# Input.net
KiCad netlist of a schematic drawn in Altium Designer
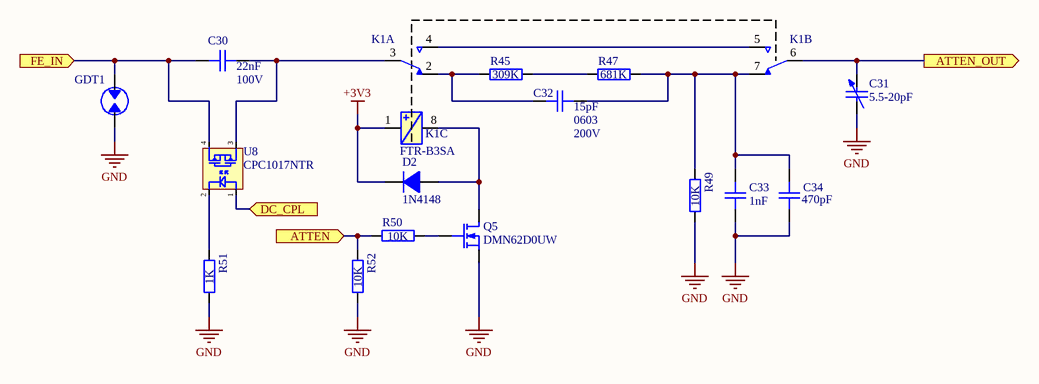
[diagram p0: Input.SchDoc]

(export (version "E")
  (design (tool "Eeschema 10.0.6"))
  (components
    (comp (ref "C30")
      (value "22nF")
      (footprint "GEN_C_0603")
      (fields (field (name "VOLTAGE RATING") "100V"))
      (libsource (lib "DSO") (part "CAP 22nF 100V X7R 0603"))
    )
    (comp (ref "C31")
      (value "5.5-20pF")
      (footprint "EW_TRIMCAP")
      (libsource (lib "DSO") (part "CAP TRIMMER 5.5-20PF 500V"))
    )
    (comp (ref "C32")
      (value "15pF")
      (footprint "GEN_C_0603")
      (fields (field (name "PACKAGE") "0603") (field (name "VOLTAGE RATING") "200V"))
      (libsource (lib "DSO") (part "CAP 15pF 200V C0G 0603"))
    )
    (comp (ref "C33")
      (value "1nF")
      (footprint "GEN_C_0402")
      (libsource (lib "DSO") (part "CAP 1nF 50V C0G 0402"))
    )
    (comp (ref "C34")
      (value "470pF")
      (footprint "GEN_C_0402")
      (libsource (lib "DSO") (part "CAP 470pF 50V C0G 0402"))
    )
    (comp (ref "D2") (value "1N4148") (footprint "GEN_SOD_323") (libsource (lib "DSO") (part "DIODE 1N4148")))
    (comp (ref "GDT1") (value "GDT") (footprint "BOU_2051") (libsource (lib "DSO") (part "GDT 90V")))
    (comp (ref "K1")
      (value "FTR-B3SA")
      (footprint "FUJ_FTR-B3SA")
      (libsource (lib "") (part "RELAY DPDT-NO FTR-B3SA_1"))
    )
    (comp (ref "Q5")
      (value "DMN62D0UW")
      (footprint "GEN_SOT_323")
      (libsource (lib "DSO") (part "NMOS DMN62D0UW"))
    )
    (comp (ref "R45")
      (value "309K")
      (footprint "GEN_R_0402")
      (fields (field (name "TOLERANCE") "1%"))
      (libsource (lib "DSO") (part "RES 309K OHM 1% 1/16W 0402"))
    )
    (comp (ref "R47")
      (value "681K")
      (footprint "GEN_R_0402")
      (fields (field (name "TOLERANCE") "1%"))
      (libsource (lib "DSO") (part "RES 681K OHM 1% 1/16W 0402"))
    )
    (comp (ref "R49")
      (value "10K")
      (footprint "GEN_R_0402")
      (fields (field (name "TOLERANCE") "1%"))
      (libsource (lib "") (part "RES 10K OHM 1% 1/10W 0402_1"))
    )
    (comp (ref "R50")
      (value "10K")
      (footprint "GEN_R_0402")
      (fields (field (name "TOLERANCE") "1%"))
      (libsource (lib "DSO") (part "RES 10K OHM 1% 1/10W 0402"))
    )
    (comp (ref "R51")
      (value "1K")
      (footprint "GEN_R_0402")
      (fields (field (name "TOLERANCE") "1%"))
      (libsource (lib "DSO") (part "RES 1K OHM 1% 1/10W 0402"))
    )
    (comp (ref "R52")
      (value "10K")
      (footprint "GEN_R_0402")
      (fields (field (name "TOLERANCE") "1%"))
      (libsource (lib "") (part "RES 10K OHM 1% 1/10W 0402_1"))
    )
    (comp (ref "U8")
      (value "CPC1017NTR")
      (footprint "IXY_CPC1017")
      (libsource (lib "DSO") (part "SSR CPC1017NTR"))
    )
  )
  (nets
    (net (code "1") (name "+3V3") (class "Default")
      (node (ref "D2") (pin "1") (pinfunction "K_1") (pintype "passive"))
      (node (ref "K1") (pin "1") (pinfunction "1_1") (pintype "passive"))
    )
    (net (code "2") (name "/ATTEN") (class "Default")
      (node (ref "R50") (pin "2") (pinfunction "2_2") (pintype "passive"))
      (node (ref "R52") (pin "2") (pinfunction "2_2") (pintype "passive"))
    )
    (net (code "3") (name "/ATTEN_OUT") (class "Default")
      (node (ref "C31") (pin "1") (pinfunction "1_1") (pintype "passive"))
      (node (ref "K1") (pin "6") (pinfunction "6_6") (pintype "passive"))
    )
    (net (code "4") (name "/DC_CPL") (class "Default")
      (node (ref "U8") (pin "1") (pinfunction "1_1") (pintype "passive"))
    )
    (net (code "5") (name "/FE_IN") (class "Default")
      (node (ref "C30") (pin "2") (pinfunction "2_2") (pintype "passive"))
      (node (ref "GDT1") (pin "1") (pinfunction "1_1") (pintype "passive"))
      (node (ref "U8") (pin "4") (pinfunction "4_4") (pintype "passive"))
    )
    (net (code "6") (name "GND") (class "Default")
      (node (ref "C31") (pin "2") (pinfunction "2_2") (pintype "passive"))
      (node (ref "C33") (pin "1") (pinfunction "1_1") (pintype "passive"))
      (node (ref "C34") (pin "1") (pinfunction "1_1") (pintype "passive"))
      (node (ref "GDT1") (pin "2") (pinfunction "2_2") (pintype "passive"))
      (node (ref "Q5") (pin "3") (pinfunction "S_3") (pintype "passive"))
      (node (ref "R49") (pin "1") (pinfunction "1_1") (pintype "passive"))
      (node (ref "R51") (pin "1") (pinfunction "1_1") (pintype "passive"))
      (node (ref "R52") (pin "1") (pinfunction "1_1") (pintype "passive"))
    )
    (net (code "7") (name "Net-(C30-Pad1)") (class "Default")
      (node (ref "C30") (pin "1") (pinfunction "1_1") (pintype "passive"))
      (node (ref "K1") (pin "3") (pinfunction "3_3") (pintype "passive"))
      (node (ref "U8") (pin "3") (pinfunction "3_3") (pintype "passive"))
    )
    (net (code "8") (name "Net-(C32-Pad1)") (class "Default")
      (node (ref "C32") (pin "1") (pinfunction "1_1") (pintype "passive"))
      (node (ref "C33") (pin "2") (pinfunction "2_2") (pintype "passive"))
      (node (ref "C34") (pin "2") (pinfunction "2_2") (pintype "passive"))
      (node (ref "K1") (pin "7") (pinfunction "7_7") (pintype "passive"))
      (node (ref "R47") (pin "2") (pinfunction "2_2") (pintype "passive"))
      (node (ref "R49") (pin "2") (pinfunction "2_2") (pintype "passive"))
    )
    (net (code "9") (name "Net-(C32-Pad2)") (class "Default")
      (node (ref "C32") (pin "2") (pinfunction "2_2") (pintype "passive"))
      (node (ref "K1") (pin "2") (pinfunction "2_2") (pintype "passive"))
      (node (ref "R45") (pin "1") (pinfunction "1_1") (pintype "passive"))
    )
    (net (code "10") (name "Net-(D2-A)") (class "Default")
      (node (ref "D2") (pin "2") (pinfunction "A_2") (pintype "passive"))
      (node (ref "K1") (pin "8") (pinfunction "8_8") (pintype "passive"))
      (node (ref "Q5") (pin "1") (pinfunction "D_1") (pintype "passive"))
    )
    (net (code "11") (name "Net-(K1-Pad4)") (class "Default")
      (node (ref "K1") (pin "4") (pinfunction "4_4") (pintype "passive"))
      (node (ref "K1") (pin "5") (pinfunction "5_5") (pintype "passive"))
    )
    (net (code "12") (name "Net-(Q5-G)") (class "Default")
      (node (ref "Q5") (pin "2") (pinfunction "G_2") (pintype "passive"))
      (node (ref "R50") (pin "1") (pinfunction "1_1") (pintype "passive"))
    )
    (net (code "13") (name "Net-(R45-Pad2)") (class "Default")
      (node (ref "R45") (pin "2") (pinfunction "2_2") (pintype "passive"))
      (node (ref "R47") (pin "1") (pinfunction "1_1") (pintype "passive"))
    )
    (net (code "14") (name "Net-(R51-Pad2)") (class "Default")
      (node (ref "R51") (pin "2") (pinfunction "2_2") (pintype "passive"))
      (node (ref "U8") (pin "2") (pinfunction "2_2") (pintype "passive"))
    )
  )
)
